# JediLightSwitch-V1_2.net
KiCad netlist of a schematic drawn in EAGLE
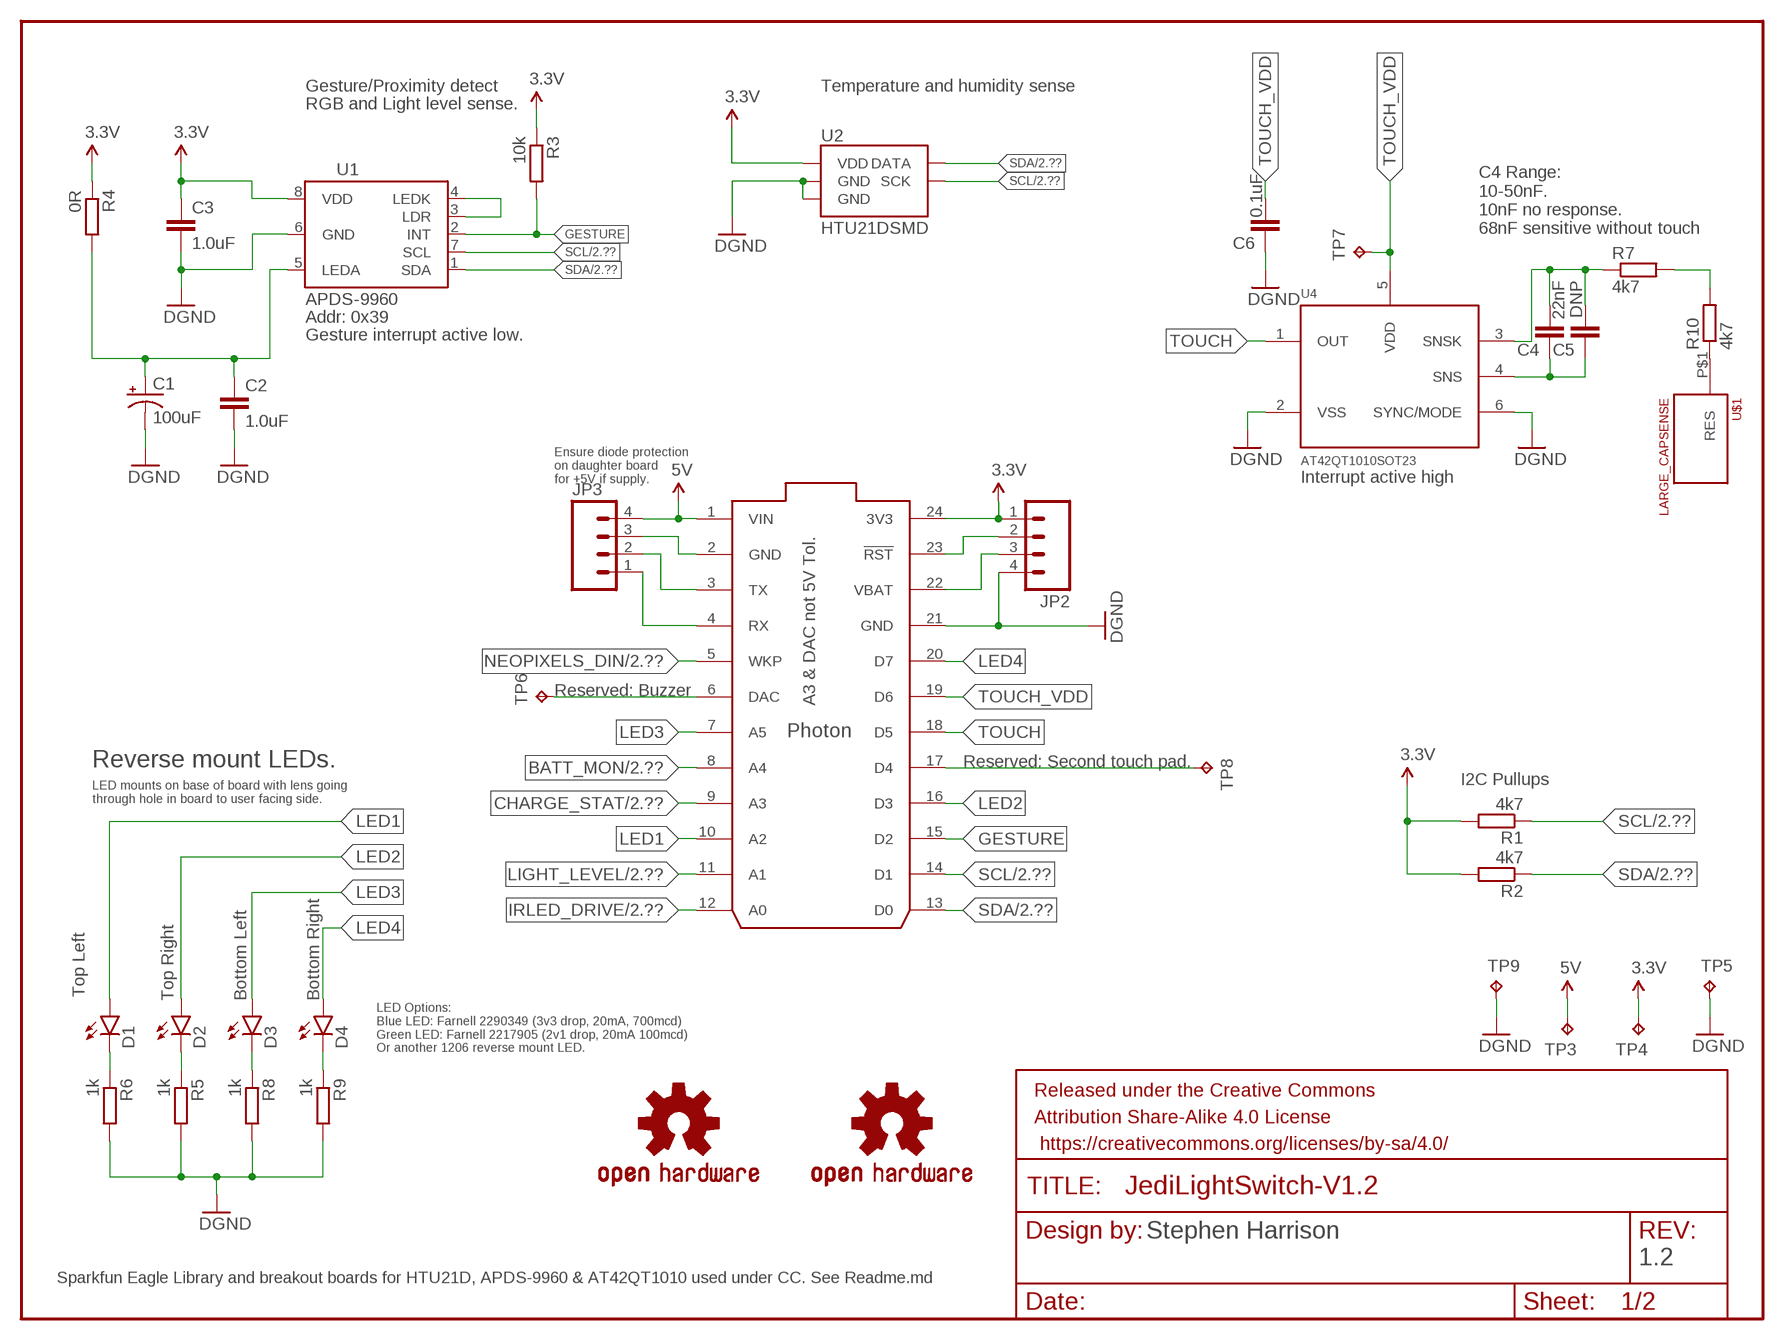
[diagram p0: schematic, sheet 1]
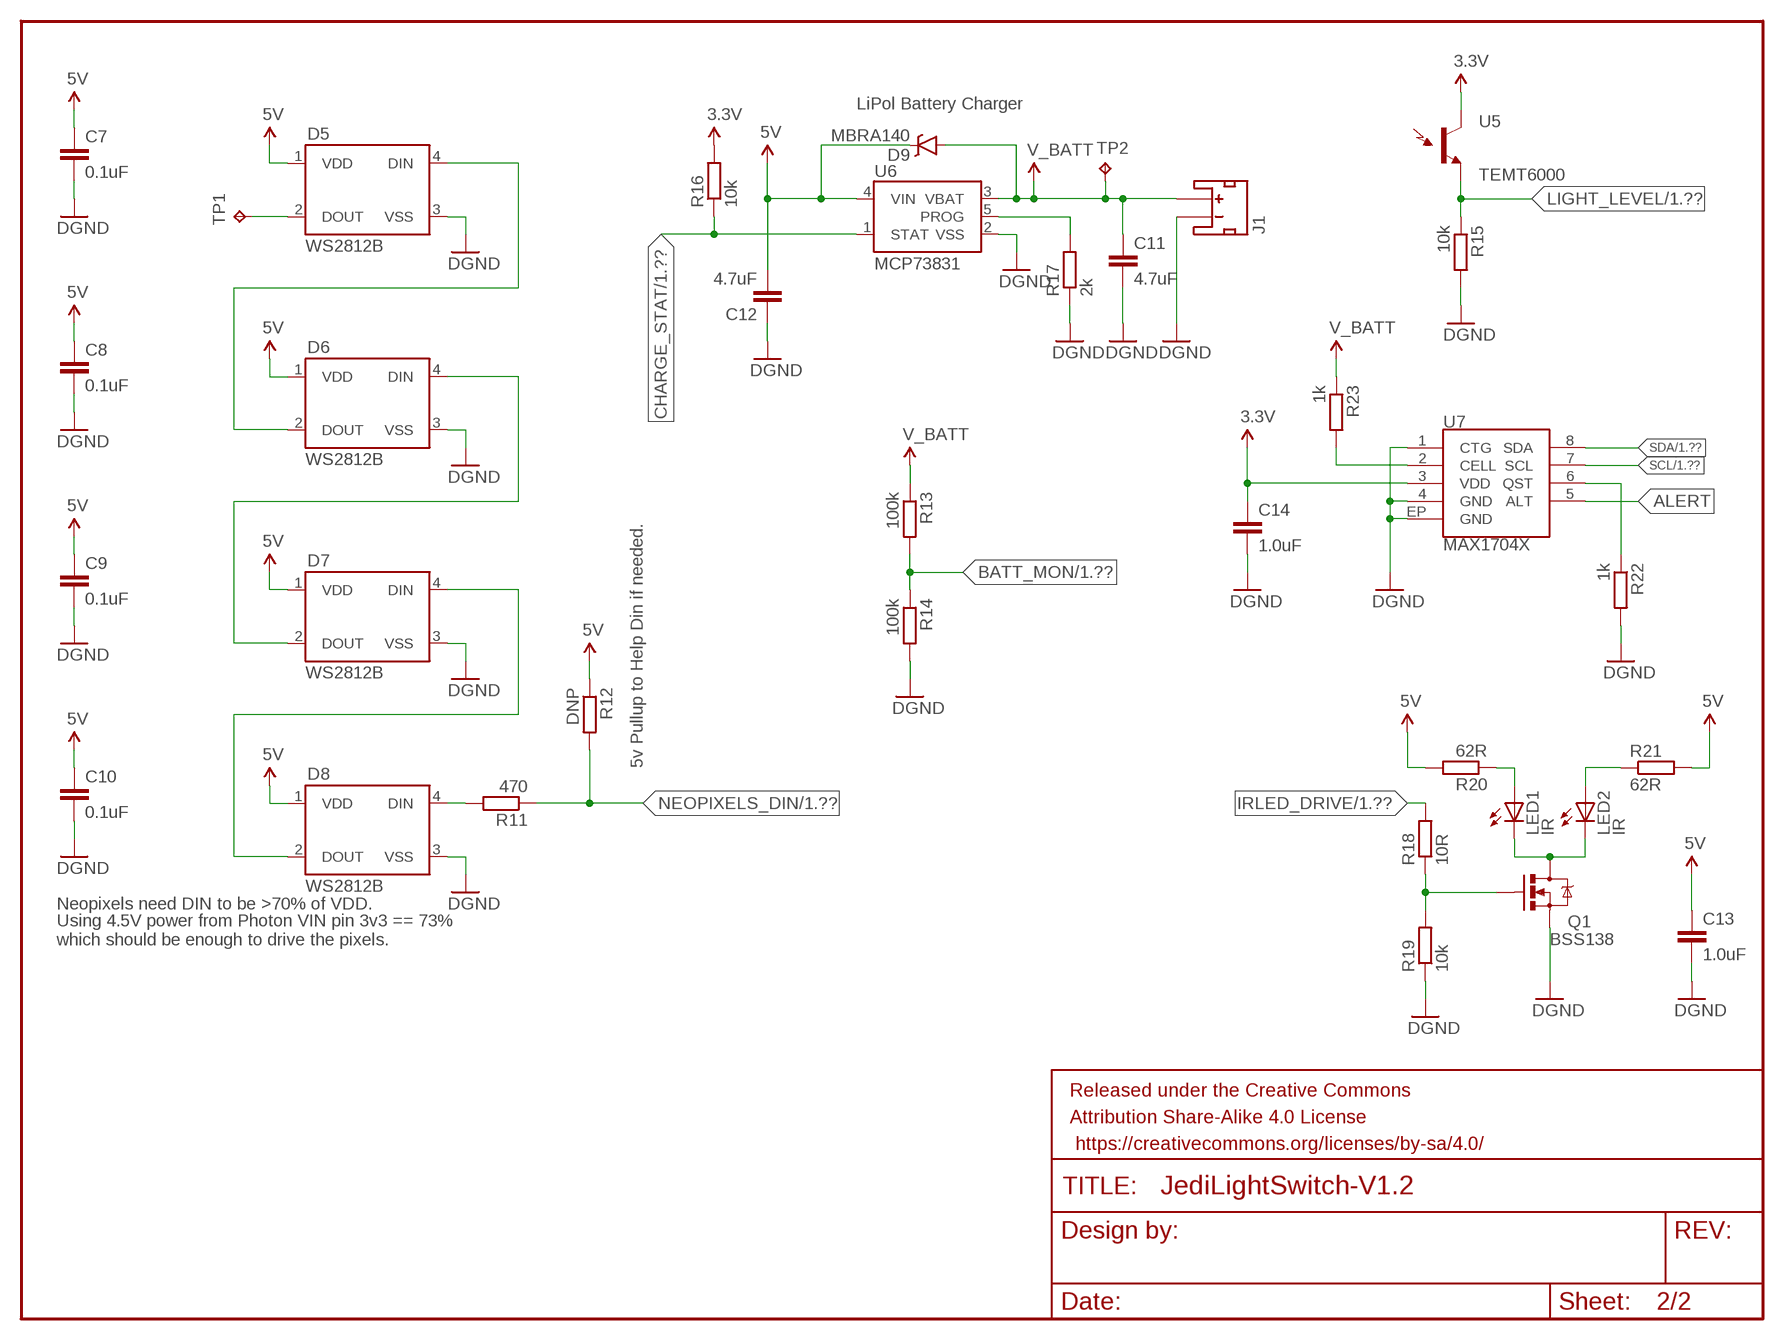
[diagram p1: schematic, sheet 2]

(export (version "E")
  (design (tool "Eeschema 10.0.6"))
  (components
    (comp (ref "C7")
      (value "0.1uF")
      (footprint "eagle-import:C0805")
      (libsource (lib "eagle-import") (part "C-EUC0805"))
    )
    (comp (ref "C8")
      (value "0.1uF")
      (footprint "eagle-import:C0805")
      (libsource (lib "eagle-import") (part "C-EUC0805"))
    )
    (comp (ref "C9")
      (value "0.1uF")
      (footprint "eagle-import:C0805")
      (libsource (lib "eagle-import") (part "C-EUC0805"))
    )
    (comp (ref "C10")
      (value "0.1uF")
      (footprint "eagle-import:C0805")
      (libsource (lib "eagle-import") (part "C-EUC0805"))
    )
    (comp (ref "C11")
      (value "4.7uF")
      (footprint "eagle-import:C0805")
      (libsource (lib "eagle-import") (part "C-EUC0805"))
    )
    (comp (ref "C12")
      (value "4.7uF")
      (footprint "eagle-import:C0805")
      (libsource (lib "eagle-import") (part "C-EUC0805"))
    )
    (comp (ref "C13")
      (value "1.0uF")
      (footprint "eagle-import:C0805")
      (libsource (lib "eagle-import") (part "C-EUC0805"))
    )
    (comp (ref "C14")
      (value "1.0uF")
      (footprint "eagle-import:C0805")
      (libsource (lib "eagle-import") (part "C-EUC0805"))
    )
    (comp (ref "D5")
      (value "WS2812B")
      (footprint "eagle-import:WS2812B")
      (libsource (lib "eagle-import") (part "WS2812B"))
    )
    (comp (ref "D6")
      (value "WS2812B")
      (footprint "eagle-import:WS2812B")
      (libsource (lib "eagle-import") (part "WS2812B"))
    )
    (comp (ref "D7")
      (value "WS2812B")
      (footprint "eagle-import:WS2812B")
      (libsource (lib "eagle-import") (part "WS2812B"))
    )
    (comp (ref "D8")
      (value "WS2812B")
      (footprint "eagle-import:WS2812B")
      (libsource (lib "eagle-import") (part "WS2812B"))
    )
    (comp (ref "D9")
      (value "MBRA140")
      (footprint "eagle-import:SMA-DIODE")
      (libsource (lib "eagle-import") (part "MBRA140"))
    )
    (comp (ref "FRAME1")
      (value "FRAME-LETTERNO_PACKAGE")
      (footprint "eagle-import:DUMMY")
      (fields (field (name "DESIGNER") "Nobody"))
      (libsource (lib "eagle-import") (part "FRAME-LETTERNO_PACKAGE"))
    )
    (comp (ref "J1")
      (value "JST_2MM_MALE")
      (footprint "eagle-import:JST-2-SMD")
      (libsource (lib "eagle-import") (part "JST_2MM_MALE"))
    )
    (comp (ref "LED1")
      (value "IR")
      (footprint "eagle-import:1206")
      (libsource (lib "eagle-import") (part "LEDSMT1206"))
    )
    (comp (ref "LED2")
      (value "IR")
      (footprint "eagle-import:1206")
      (libsource (lib "eagle-import") (part "LEDSMT1206"))
    )
    (comp (ref "Q1")
      (value "BSS138")
      (footprint "eagle-import:SOT23-3")
      (libsource (lib "eagle-import") (part "MOSFET-NCHANNELAO3404A"))
    )
    (comp (ref "R11")
      (value "470")
      (footprint "eagle-import:R0805")
      (libsource (lib "eagle-import") (part "R-EU_R0805"))
    )
    (comp (ref "R12")
      (value "DNP")
      (footprint "eagle-import:R0805")
      (libsource (lib "eagle-import") (part "R-EU_R0805"))
    )
    (comp (ref "R13")
      (value "100k")
      (footprint "eagle-import:R0805")
      (libsource (lib "eagle-import") (part "R-EU_R0805"))
    )
    (comp (ref "R14")
      (value "100k")
      (footprint "eagle-import:R0805")
      (libsource (lib "eagle-import") (part "R-EU_R0805"))
    )
    (comp (ref "R15")
      (value "10k")
      (footprint "eagle-import:R0805")
      (libsource (lib "eagle-import") (part "R-EU_R0805"))
    )
    (comp (ref "R16")
      (value "10k")
      (footprint "eagle-import:R0805")
      (libsource (lib "eagle-import") (part "R-EU_R0805"))
    )
    (comp (ref "R17")
      (value "2k")
      (footprint "eagle-import:R0805")
      (libsource (lib "eagle-import") (part "R-EU_R0805"))
    )
    (comp (ref "R18")
      (value "10R")
      (footprint "eagle-import:R0805")
      (libsource (lib "eagle-import") (part "R-EU_R0805"))
    )
    (comp (ref "R19")
      (value "10k")
      (footprint "eagle-import:R0805")
      (libsource (lib "eagle-import") (part "R-EU_R0805"))
    )
    (comp (ref "R20")
      (value "62R")
      (footprint "eagle-import:R0805")
      (libsource (lib "eagle-import") (part "R-EU_R0805"))
    )
    (comp (ref "R21")
      (value "62R")
      (footprint "eagle-import:R0805")
      (libsource (lib "eagle-import") (part "R-EU_R0805"))
    )
    (comp (ref "R22")
      (value "1k")
      (footprint "eagle-import:R0805")
      (libsource (lib "eagle-import") (part "R-EU_R0805"))
    )
    (comp (ref "R23")
      (value "1k")
      (footprint "eagle-import:R0805")
      (libsource (lib "eagle-import") (part "R-EU_R0805"))
    )
    (comp (ref "TP1")
      (value "TPTP20R")
      (footprint "eagle-import:TP20R")
      (libsource (lib "eagle-import") (part "TPTP20R"))
    )
    (comp (ref "TP2")
      (value "TPTP20R")
      (footprint "eagle-import:TP20R")
      (libsource (lib "eagle-import") (part "TPTP20R"))
    )
    (comp (ref "U5")
      (value "TEMT6000")
      (footprint "eagle-import:TEMT6000-SEN")
      (libsource (lib "eagle-import") (part "LIGHTSENSORTEMT6000"))
    )
    (comp (ref "U6")
      (value "MCP73831")
      (footprint "eagle-import:SOT23-5")
      (libsource (lib "eagle-import") (part "MCP73831"))
    )
    (comp (ref "U7")
      (value "MAX1704X")
      (footprint "eagle-import:TDFN-8")
      (libsource (lib "eagle-import") (part "MAX1704X"))
    )
    (comp (ref "C1")
      (value "100uF")
      (footprint "eagle-import:EIA7343")
      (libsource (lib "eagle-import") (part "100UF-10V-10%(TANT)"))
    )
    (comp (ref "C2")
      (value "1.0uF")
      (footprint "eagle-import:C0805")
      (libsource (lib "eagle-import") (part "C-EUC0805"))
    )
    (comp (ref "C3")
      (value "1.0uF")
      (footprint "eagle-import:C0805")
      (libsource (lib "eagle-import") (part "C-EUC0805"))
    )
    (comp (ref "C4")
      (value "22nF")
      (footprint "eagle-import:C0805")
      (libsource (lib "eagle-import") (part "C-EUC0805"))
    )
    (comp (ref "C5")
      (value "DNP")
      (footprint "eagle-import:C0805")
      (libsource (lib "eagle-import") (part "C-EUC0805"))
    )
    (comp (ref "C6")
      (value "0.1uF")
      (footprint "eagle-import:C0805")
      (libsource (lib "eagle-import") (part "C-EUC0805"))
    )
    (comp (ref "D1")
      (value "LED1206-BOTTOM")
      (footprint "eagle-import:LED-1206-BOTTOM")
      (libsource (lib "eagle-import") (part "LED1206-BOTTOM"))
    )
    (comp (ref "D2")
      (value "LED1206-BOTTOM")
      (footprint "eagle-import:LED-1206-BOTTOM")
      (libsource (lib "eagle-import") (part "LED1206-BOTTOM"))
    )
    (comp (ref "D3")
      (value "LED1206-BOTTOM")
      (footprint "eagle-import:LED-1206-BOTTOM")
      (libsource (lib "eagle-import") (part "LED1206-BOTTOM"))
    )
    (comp (ref "D4")
      (value "LED1206-BOTTOM")
      (footprint "eagle-import:LED-1206-BOTTOM")
      (libsource (lib "eagle-import") (part "LED1206-BOTTOM"))
    )
    (comp (ref "FRAME2")
      (value "FRAME-LETTER")
      (footprint "eagle-import:CREATIVE_COMMONS")
      (libsource (lib "eagle-import") (part "FRAME-LETTER"))
    )
    (comp (ref "JP2")
      (value "M04SMD_STRAIGHT_COMBO")
      (footprint "eagle-import:1X04_SMD_STRAIGHT_COMBO")
      (libsource (lib "eagle-import") (part "M04SMD_STRAIGHT_COMBO"))
    )
    (comp (ref "JP3")
      (value "M04SMD_STRAIGHT_COMBO")
      (footprint "eagle-import:1X04_SMD_STRAIGHT_COMBO")
      (libsource (lib "eagle-import") (part "M04SMD_STRAIGHT_COMBO"))
    )
    (comp (ref "LOGO1")
      (value "OSHW-LOGOM")
      (footprint "eagle-import:OSHW-LOGO-M")
      (libsource (lib "eagle-import") (part "OSHW-LOGOM"))
    )
    (comp (ref "LOGO2")
      (value "OSHW-LOGOM")
      (footprint "eagle-import:OSHW-LOGO-M")
      (libsource (lib "eagle-import") (part "OSHW-LOGOM"))
    )
    (comp (ref "R1")
      (value "4k7")
      (footprint "eagle-import:R0805")
      (libsource (lib "eagle-import") (part "R-EU_R0805"))
    )
    (comp (ref "R2")
      (value "4k7")
      (footprint "eagle-import:R0805")
      (libsource (lib "eagle-import") (part "R-EU_R0805"))
    )
    (comp (ref "R3")
      (value "10k")
      (footprint "eagle-import:R0805")
      (libsource (lib "eagle-import") (part "R-EU_R0805"))
    )
    (comp (ref "R4")
      (value "0R")
      (footprint "eagle-import:R0805")
      (libsource (lib "eagle-import") (part "R-EU_R0805"))
    )
    (comp (ref "R5")
      (value "1k")
      (footprint "eagle-import:R0805")
      (libsource (lib "eagle-import") (part "R-EU_R0805"))
    )
    (comp (ref "R6")
      (value "1k")
      (footprint "eagle-import:R0805")
      (libsource (lib "eagle-import") (part "R-EU_R0805"))
    )
    (comp (ref "R7")
      (value "4k7")
      (footprint "eagle-import:R0805")
      (libsource (lib "eagle-import") (part "R-EU_R0805"))
    )
    (comp (ref "R8")
      (value "1k")
      (footprint "eagle-import:R0805")
      (libsource (lib "eagle-import") (part "R-EU_R0805"))
    )
    (comp (ref "R9")
      (value "1k")
      (footprint "eagle-import:R0805")
      (libsource (lib "eagle-import") (part "R-EU_R0805"))
    )
    (comp (ref "R10")
      (value "4k7")
      (footprint "eagle-import:R0805")
      (libsource (lib "eagle-import") (part "R-EU_R0805"))
    )
    (comp (ref "TP3")
      (value "TPTP20R")
      (footprint "eagle-import:TP20R")
      (libsource (lib "eagle-import") (part "TPTP20R"))
    )
    (comp (ref "TP4")
      (value "3v3")
      (footprint "eagle-import:TP20R")
      (libsource (lib "eagle-import") (part "TPTP20R"))
    )
    (comp (ref "TP5")
      (value "TPTP20R")
      (footprint "eagle-import:TP20R")
      (libsource (lib "eagle-import") (part "TPTP20R"))
    )
    (comp (ref "TP6")
      (value "TPTP20R")
      (footprint "eagle-import:TP20R")
      (libsource (lib "eagle-import") (part "TPTP20R"))
    )
    (comp (ref "TP7")
      (value "TPTP20R")
      (footprint "eagle-import:TP20R")
      (libsource (lib "eagle-import") (part "TPTP20R"))
    )
    (comp (ref "TP8")
      (value "TPTP20R")
      (footprint "eagle-import:TP20R")
      (libsource (lib "eagle-import") (part "TPTP20R"))
    )
    (comp (ref "TP9")
      (value "TPTP20R")
      (footprint "eagle-import:TP20R")
      (libsource (lib "eagle-import") (part "TPTP20R"))
    )
    (comp (ref "U$1")
      (value "LARGE_CAPSENSE")
      (footprint "eagle-import:LARGE_CAPSENSE")
      (libsource (lib "eagle-import") (part "LARGE_CAPSENSE"))
    )
    (comp (ref "U1")
      (value "APDS-9960")
      (footprint "eagle-import:APDS-9960")
      (libsource (lib "eagle-import") (part "APDS-9960"))
    )
    (comp (ref "U2")
      (value "HTU21DSMD")
      (footprint "eagle-import:HTU21D")
      (libsource (lib "eagle-import") (part "HTU21DSMD"))
    )
    (comp (ref "U3")
      (value "PHOTON_SMD")
      (footprint "eagle-import:PHOTON_SMD")
      (libsource (lib "eagle-import") (part "PHOTON_SMD"))
    )
    (comp (ref "U4")
      (value "AT42QT1010SOT23")
      (footprint "eagle-import:SOT23-6")
      (libsource (lib "eagle-import") (part "AT42QT1010SOT23"))
    )
  )
  (nets
    (net (code "1") (name "3.3V") (class "Default")
      (node (ref "C14") (pin "1") (pinfunction "1_1") (pintype "passive"))
      (node (ref "C3") (pin "1") (pinfunction "1_1") (pintype "passive"))
      (node (ref "JP2") (pin "1") (pinfunction "1_1") (pintype "passive"))
      (node (ref "R1") (pin "2") (pinfunction "2_2") (pintype "passive"))
      (node (ref "R16") (pin "2") (pinfunction "2_2") (pintype "passive"))
      (node (ref "R2") (pin "2") (pinfunction "2_2") (pintype "passive"))
      (node (ref "R3") (pin "1") (pinfunction "1_1") (pintype "passive"))
      (node (ref "R4") (pin "1") (pinfunction "1_1") (pintype "passive"))
      (node (ref "TP4") (pin "TP") (pinfunction "TP_TP") (pintype "input"))
      (node (ref "U1") (pin "8") (pinfunction "VDD_8") (pintype "bidirectional"))
      (node (ref "U2") (pin "VDD") (pinfunction "VDD_VDD") (pintype "power_in"))
      (node (ref "U3") (pin "24") (pinfunction "3V3_24") (pintype "power_in"))
      (node (ref "U5") (pin "COLLECTOR") (pinfunction "C1_COLLECTOR") (pintype "passive"))
      (node (ref "U7") (pin "3") (pinfunction "VDD_3") (pintype "bidirectional"))
    )
    (net (code "2") (name "5V") (class "Default")
      (node (ref "C10") (pin "1") (pinfunction "1_1") (pintype "passive"))
      (node (ref "C12") (pin "2") (pinfunction "2_2") (pintype "passive"))
      (node (ref "C13") (pin "1") (pinfunction "1_1") (pintype "passive"))
      (node (ref "C7") (pin "1") (pinfunction "1_1") (pintype "passive"))
      (node (ref "C8") (pin "1") (pinfunction "1_1") (pintype "passive"))
      (node (ref "C9") (pin "1") (pinfunction "1_1") (pintype "passive"))
      (node (ref "D5") (pin "1") (pinfunction "VDD_1") (pintype "power_in"))
      (node (ref "D6") (pin "1") (pinfunction "VDD_1") (pintype "power_in"))
      (node (ref "D7") (pin "1") (pinfunction "VDD_1") (pintype "power_in"))
      (node (ref "D8") (pin "1") (pinfunction "VDD_1") (pintype "power_in"))
      (node (ref "D9") (pin "C") (pinfunction "C_C") (pintype "passive"))
      (node (ref "JP3") (pin "4") (pinfunction "4_4") (pintype "passive"))
      (node (ref "R12") (pin "1") (pinfunction "1_1") (pintype "passive"))
      (node (ref "R20") (pin "2") (pinfunction "2_2") (pintype "passive"))
      (node (ref "R21") (pin "2") (pinfunction "2_2") (pintype "passive"))
      (node (ref "TP3") (pin "TP") (pinfunction "TP_TP") (pintype "input"))
      (node (ref "U3") (pin "1") (pinfunction "VIN_1") (pintype "power_in"))
      (node (ref "U6") (pin "4") (pinfunction "VIN_4") (pintype "power_in"))
    )
    (net (code "3") (name "ALERT") (class "Default")
      (node (ref "U7") (pin "5") (pinfunction "ALT_5") (pintype "bidirectional"))
    )
    (net (code "4") (name "BATT_MON") (class "Default")
      (node (ref "R13") (pin "2") (pinfunction "2_2") (pintype "passive"))
      (node (ref "R14") (pin "1") (pinfunction "1_1") (pintype "passive"))
      (node (ref "U3") (pin "8") (pinfunction "A4_8") (pintype "bidirectional"))
    )
    (net (code "5") (name "CHARGE_STAT") (class "Default")
      (node (ref "R16") (pin "1") (pinfunction "1_1") (pintype "passive"))
      (node (ref "U3") (pin "9") (pinfunction "A3_9") (pintype "bidirectional"))
      (node (ref "U6") (pin "1") (pinfunction "STAT_1") (pintype "output"))
    )
    (net (code "6") (name "GESTURE") (class "Default")
      (node (ref "R3") (pin "2") (pinfunction "2_2") (pintype "passive"))
      (node (ref "U1") (pin "2") (pinfunction "INT_2") (pintype "bidirectional"))
      (node (ref "U3") (pin "15") (pinfunction "D2_15") (pintype "bidirectional"))
    )
    (net (code "7") (name "GND") (class "Default")
      (node (ref "C1") (pin "C") (pinfunction "-_C") (pintype "passive"))
      (node (ref "C10") (pin "2") (pinfunction "2_2") (pintype "passive"))
      (node (ref "C11") (pin "2") (pinfunction "2_2") (pintype "passive"))
      (node (ref "C12") (pin "1") (pinfunction "1_1") (pintype "passive"))
      (node (ref "C13") (pin "2") (pinfunction "2_2") (pintype "passive"))
      (node (ref "C14") (pin "2") (pinfunction "2_2") (pintype "passive"))
      (node (ref "C2") (pin "2") (pinfunction "2_2") (pintype "passive"))
      (node (ref "C3") (pin "2") (pinfunction "2_2") (pintype "passive"))
      (node (ref "C6") (pin "1") (pinfunction "1_1") (pintype "passive"))
      (node (ref "C7") (pin "2") (pinfunction "2_2") (pintype "passive"))
      (node (ref "C8") (pin "2") (pinfunction "2_2") (pintype "passive"))
      (node (ref "C9") (pin "2") (pinfunction "2_2") (pintype "passive"))
      (node (ref "D5") (pin "3") (pinfunction "VSS_3") (pintype "power_in"))
      (node (ref "D6") (pin "3") (pinfunction "VSS_3") (pintype "power_in"))
      (node (ref "D7") (pin "3") (pinfunction "VSS_3") (pintype "power_in"))
      (node (ref "D8") (pin "3") (pinfunction "VSS_3") (pintype "power_in"))
      (node (ref "J1") (pin "1") (pinfunction "-_1") (pintype "bidirectional"))
      (node (ref "JP2") (pin "4") (pinfunction "4_4") (pintype "passive"))
      (node (ref "JP3") (pin "3") (pinfunction "3_3") (pintype "passive"))
      (node (ref "Q1") (pin "2") (pinfunction "S_2") (pintype "passive"))
      (node (ref "R14") (pin "2") (pinfunction "2_2") (pintype "passive"))
      (node (ref "R15") (pin "2") (pinfunction "2_2") (pintype "passive"))
      (node (ref "R17") (pin "1") (pinfunction "1_1") (pintype "passive"))
      (node (ref "R19") (pin "1") (pinfunction "1_1") (pintype "passive"))
      (node (ref "R22") (pin "2") (pinfunction "2_2") (pintype "passive"))
      (node (ref "R5") (pin "2") (pinfunction "2_2") (pintype "passive"))
      (node (ref "R6") (pin "2") (pinfunction "2_2") (pintype "passive"))
      (node (ref "R8") (pin "2") (pinfunction "2_2") (pintype "passive"))
      (node (ref "R9") (pin "2") (pinfunction "2_2") (pintype "passive"))
      (node (ref "TP5") (pin "TP") (pinfunction "TP_TP") (pintype "input"))
      (node (ref "TP9") (pin "TP") (pinfunction "TP_TP") (pintype "input"))
      (node (ref "U1") (pin "6") (pinfunction "GND_6") (pintype "bidirectional"))
      (node (ref "U2") (pin "7") (pinfunction "GND_7") (pintype "power_in"))
      (node (ref "U2") (pin "GND") (pinfunction "GND_GND") (pintype "power_in"))
      (node (ref "U3") (pin "2") (pinfunction "GND_2") (pintype "power_in"))
      (node (ref "U3") (pin "21") (pinfunction "GND_21") (pintype "power_in"))
      (node (ref "U4") (pin "2") (pinfunction "VSS_2") (pintype "bidirectional"))
      (node (ref "U4") (pin "6") (pinfunction "SYNC/MODE_6") (pintype "bidirectional"))
      (node (ref "U6") (pin "2") (pinfunction "VSS_2") (pintype "power_in"))
      (node (ref "U7") (pin "1") (pinfunction "CTG_1") (pintype "bidirectional"))
      (node (ref "U7") (pin "4") (pinfunction "GND_4") (pintype "bidirectional"))
      (node (ref "U7") (pin "EP") (pinfunction "GND_EP") (pintype "bidirectional"))
    )
    (net (code "8") (name "IRLED_DRIVE") (class "Default")
      (node (ref "R18") (pin "2") (pinfunction "2_2") (pintype "passive"))
      (node (ref "U3") (pin "12") (pinfunction "A0_12") (pintype "bidirectional"))
    )
    (net (code "9") (name "LED1") (class "Default")
      (node (ref "D1") (pin "A") (pinfunction "A_A") (pintype "passive"))
      (node (ref "U3") (pin "10") (pinfunction "A2_10") (pintype "bidirectional"))
    )
    (net (code "10") (name "LED2") (class "Default")
      (node (ref "D2") (pin "A") (pinfunction "A_A") (pintype "passive"))
      (node (ref "U3") (pin "16") (pinfunction "D3_16") (pintype "bidirectional"))
    )
    (net (code "11") (name "LED3") (class "Default")
      (node (ref "D3") (pin "A") (pinfunction "A_A") (pintype "passive"))
      (node (ref "U3") (pin "7") (pinfunction "A5_7") (pintype "bidirectional"))
    )
    (net (code "12") (name "LED4") (class "Default")
      (node (ref "D4") (pin "A") (pinfunction "A_A") (pintype "passive"))
      (node (ref "U3") (pin "20") (pinfunction "D7_20") (pintype "bidirectional"))
    )
    (net (code "13") (name "LIGHT_LEVEL") (class "Default")
      (node (ref "R15") (pin "1") (pinfunction "1_1") (pintype "passive"))
      (node (ref "U3") (pin "11") (pinfunction "A1_11") (pintype "bidirectional"))
      (node (ref "U5") (pin "EMITTER") (pinfunction "E1_EMITTER") (pintype "passive"))
    )
    (net (code "14") (name "NEOPIXELS_DIN") (class "Default")
      (node (ref "R11") (pin "1") (pinfunction "1_1") (pintype "passive"))
      (node (ref "R12") (pin "2") (pinfunction "2_2") (pintype "passive"))
      (node (ref "U3") (pin "5") (pinfunction "WKP_5") (pintype "bidirectional"))
    )
    (net (code "15") (name "Net-(C1-+)") (class "Default")
      (node (ref "C1") (pin "A") (pinfunction "+_A") (pintype "passive"))
      (node (ref "C2") (pin "1") (pinfunction "1_1") (pintype "passive"))
      (node (ref "R4") (pin "2") (pinfunction "2_2") (pintype "passive"))
      (node (ref "U1") (pin "5") (pinfunction "LEDA_5") (pintype "bidirectional"))
    )
    (net (code "16") (name "Net-(D1-PadC)") (class "Default")
      (node (ref "D1") (pin "C") (pinfunction "C_C") (pintype "passive"))
      (node (ref "R6") (pin "1") (pinfunction "1_1") (pintype "passive"))
    )
    (net (code "17") (name "Net-(D2-PadC)") (class "Default")
      (node (ref "D2") (pin "C") (pinfunction "C_C") (pintype "passive"))
      (node (ref "R5") (pin "1") (pinfunction "1_1") (pintype "passive"))
    )
    (net (code "18") (name "Net-(D3-PadC)") (class "Default")
      (node (ref "D3") (pin "C") (pinfunction "C_C") (pintype "passive"))
      (node (ref "R8") (pin "1") (pinfunction "1_1") (pintype "passive"))
    )
    (net (code "19") (name "Net-(D4-PadC)") (class "Default")
      (node (ref "D4") (pin "C") (pinfunction "C_C") (pintype "passive"))
      (node (ref "R9") (pin "1") (pinfunction "1_1") (pintype "passive"))
    )
    (net (code "20") (name "Net-(D5-DIN)") (class "Default")
      (node (ref "D5") (pin "4") (pinfunction "DIN_4") (pintype "input"))
      (node (ref "D6") (pin "2") (pinfunction "DOUT_2") (pintype "output"))
    )
    (net (code "21") (name "Net-(D5-DOUT)") (class "Default")
      (node (ref "D5") (pin "2") (pinfunction "DOUT_2") (pintype "output"))
      (node (ref "TP1") (pin "TP") (pinfunction "TP_TP") (pintype "input"))
    )
    (net (code "22") (name "Net-(D6-DIN)") (class "Default")
      (node (ref "D6") (pin "4") (pinfunction "DIN_4") (pintype "input"))
      (node (ref "D7") (pin "2") (pinfunction "DOUT_2") (pintype "output"))
    )
    (net (code "23") (name "Net-(D7-DIN)") (class "Default")
      (node (ref "D7") (pin "4") (pinfunction "DIN_4") (pintype "input"))
      (node (ref "D8") (pin "2") (pinfunction "DOUT_2") (pintype "output"))
    )
    (net (code "24") (name "Net-(D8-DIN)") (class "Default")
      (node (ref "D8") (pin "4") (pinfunction "DIN_4") (pintype "input"))
      (node (ref "R11") (pin "2") (pinfunction "2_2") (pintype "passive"))
    )
    (net (code "25") (name "Net-(LED1-PadA)") (class "Default")
      (node (ref "LED1") (pin "A") (pinfunction "A_A") (pintype "passive"))
      (node (ref "R20") (pin "1") (pinfunction "1_1") (pintype "passive"))
    )
    (net (code "26") (name "Net-(LED2-PadA)") (class "Default")
      (node (ref "LED2") (pin "A") (pinfunction "A_A") (pintype "passive"))
      (node (ref "R21") (pin "1") (pinfunction "1_1") (pintype "passive"))
    )
    (net (code "27") (name "Net-(Q1-D)") (class "Default")
      (node (ref "LED1") (pin "C") (pinfunction "C_C") (pintype "passive"))
      (node (ref "LED2") (pin "C") (pinfunction "C_C") (pintype "passive"))
      (node (ref "Q1") (pin "3") (pinfunction "D_3") (pintype "passive"))
    )
    (net (code "28") (name "Net-(Q1-G)") (class "Default")
      (node (ref "Q1") (pin "1") (pinfunction "G_1") (pintype "passive"))
      (node (ref "R18") (pin "1") (pinfunction "1_1") (pintype "passive"))
      (node (ref "R19") (pin "2") (pinfunction "2_2") (pintype "passive"))
    )
    (net (code "29") (name "Net-(R10-Pad2)") (class "Default")
      (node (ref "R10") (pin "2") (pinfunction "2_2") (pintype "passive"))
      (node (ref "R7") (pin "2") (pinfunction "2_2") (pintype "passive"))
    )
    (net (code "30") (name "Net-(U$1-RES)") (class "Default")
      (node (ref "R10") (pin "1") (pinfunction "1_1") (pintype "passive"))
      (node (ref "U$1") (pin "P$1") (pinfunction "RES_P$1") (pintype "bidirectional"))
    )
    (net (code "31") (name "Net-(U1-LDR)") (class "Default")
      (node (ref "U1") (pin "3") (pinfunction "LDR_3") (pintype "bidirectional"))
      (node (ref "U1") (pin "4") (pinfunction "LEDK_4") (pintype "bidirectional"))
    )
    (net (code "32") (name "Net-(U3A-D4)") (class "Default")
      (node (ref "TP8") (pin "TP") (pinfunction "TP_TP") (pintype "input"))
      (node (ref "U3") (pin "17") (pinfunction "D4_17") (pintype "bidirectional"))
    )
    (net (code "33") (name "Net-(U3A-DAC)") (class "Default")
      (node (ref "TP6") (pin "TP") (pinfunction "TP_TP") (pintype "input"))
      (node (ref "U3") (pin "6") (pinfunction "DAC_6") (pintype "bidirectional"))
    )
    (net (code "34") (name "Net-(U3A-RX)") (class "Default")
      (node (ref "JP3") (pin "1") (pinfunction "1_1") (pintype "passive"))
      (node (ref "U3") (pin "4") (pinfunction "RX_4") (pintype "bidirectional"))
    )
    (net (code "35") (name "Net-(U3A-TX)") (class "Default")
      (node (ref "JP3") (pin "2") (pinfunction "2_2") (pintype "passive"))
      (node (ref "U3") (pin "3") (pinfunction "TX_3") (pintype "bidirectional"))
    )
    (net (code "36") (name "Net-(U3A-VBAT)") (class "Default")
      (node (ref "JP2") (pin "3") (pinfunction "3_3") (pintype "passive"))
      (node (ref "U3") (pin "22") (pinfunction "VBAT_22") (pintype "power_in"))
    )
    (net (code "37") (name "Net-(U3A-~{RST})") (class "Default")
      (node (ref "JP2") (pin "2") (pinfunction "2_2") (pintype "passive"))
      (node (ref "U3") (pin "23") (pinfunction "~{RST}_23") (pintype "bidirectional"))
    )
    (net (code "38") (name "Net-(U4-SNS)") (class "Default")
      (node (ref "C4") (pin "1") (pinfunction "1_1") (pintype "passive"))
      (node (ref "C5") (pin "1") (pinfunction "1_1") (pintype "passive"))
      (node (ref "U4") (pin "4") (pinfunction "SNS_4") (pintype "bidirectional"))
    )
    (net (code "39") (name "Net-(U4-SNSK)") (class "Default")
      (node (ref "C4") (pin "2") (pinfunction "2_2") (pintype "passive"))
      (node (ref "C5") (pin "2") (pinfunction "2_2") (pintype "passive"))
      (node (ref "R7") (pin "1") (pinfunction "1_1") (pintype "passive"))
      (node (ref "U4") (pin "3") (pinfunction "SNSK_3") (pintype "bidirectional"))
    )
    (net (code "40") (name "Net-(U6-PROG)") (class "Default")
      (node (ref "R17") (pin "2") (pinfunction "2_2") (pintype "passive"))
      (node (ref "U6") (pin "5") (pinfunction "PROG_5") (pintype "input"))
    )
    (net (code "41") (name "Net-(U7-CELL)") (class "Default")
      (node (ref "R23") (pin "2") (pinfunction "2_2") (pintype "passive"))
      (node (ref "U7") (pin "2") (pinfunction "CELL_2") (pintype "bidirectional"))
    )
    (net (code "42") (name "Net-(U7-QST)") (class "Default")
      (node (ref "R22") (pin "1") (pinfunction "1_1") (pintype "passive"))
      (node (ref "U7") (pin "6") (pinfunction "QST_6") (pintype "bidirectional"))
    )
    (net (code "43") (name "SCL") (class "Default")
      (node (ref "R1") (pin "1") (pinfunction "1_1") (pintype "passive"))
      (node (ref "U1") (pin "7") (pinfunction "SCL_7") (pintype "bidirectional"))
      (node (ref "U2") (pin "SCK") (pinfunction "SCK_SCK") (pintype "input"))
      (node (ref "U3") (pin "14") (pinfunction "D1_14") (pintype "bidirectional"))
      (node (ref "U7") (pin "7") (pinfunction "SCL_7") (pintype "bidirectional"))
    )
    (net (code "44") (name "SDA") (class "Default")
      (node (ref "R2") (pin "1") (pinfunction "1_1") (pintype "passive"))
      (node (ref "U1") (pin "1") (pinfunction "SDA_1") (pintype "bidirectional"))
      (node (ref "U2") (pin "DATA") (pinfunction "DATA_DATA") (pintype "bidirectional"))
      (node (ref "U3") (pin "13") (pinfunction "D0_13") (pintype "bidirectional"))
      (node (ref "U7") (pin "8") (pinfunction "SDA_8") (pintype "bidirectional"))
    )
    (net (code "45") (name "TOUCH") (class "Default")
      (node (ref "U3") (pin "18") (pinfunction "D5_18") (pintype "bidirectional"))
      (node (ref "U4") (pin "1") (pinfunction "OUT_1") (pintype "bidirectional"))
    )
    (net (code "46") (name "TOUCH_VDD") (class "Default")
      (node (ref "C6") (pin "2") (pinfunction "2_2") (pintype "passive"))
      (node (ref "TP7") (pin "TP") (pinfunction "TP_TP") (pintype "input"))
      (node (ref "U3") (pin "19") (pinfunction "D6_19") (pintype "bidirectional"))
      (node (ref "U4") (pin "5") (pinfunction "VDD_5") (pintype "bidirectional"))
    )
    (net (code "47") (name "V_BATT") (class "Default")
      (node (ref "C11") (pin "1") (pinfunction "1_1") (pintype "passive"))
      (node (ref "D9") (pin "A") (pinfunction "A_A") (pintype "passive"))
      (node (ref "J1") (pin "2") (pinfunction "+_2") (pintype "bidirectional"))
      (node (ref "R13") (pin "1") (pinfunction "1_1") (pintype "passive"))
      (node (ref "R23") (pin "1") (pinfunction "1_1") (pintype "passive"))
      (node (ref "TP2") (pin "TP") (pinfunction "TP_TP") (pintype "input"))
      (node (ref "U6") (pin "3") (pinfunction "VBAT_3") (pintype "power_in"))
    )
    (net (code "48") (name "unconnected-(J1-PAD1-PadNC1)") (class "Default")
      (node (ref "J1") (pin "NC1") (pinfunction "PAD1_NC1") (pintype "bidirectional"))
    )
    (net (code "49") (name "unconnected-(J1-PAD2-PadNC2)") (class "Default")
      (node (ref "J1") (pin "NC2") (pinfunction "PAD2_NC2") (pintype "bidirectional"))
    )
  )
)
